# IEEEAdapter_v2.net
KiCad netlist of a schematic drawn in EAGLE
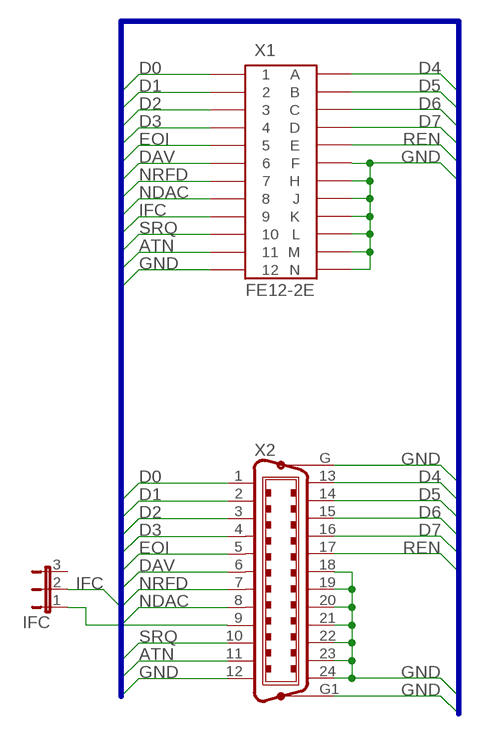
[diagram p0: schematic, sheet 1]

(export (version "E")
  (design (tool "Eeschema 10.0.6"))
  (components
    (comp (ref "IFC")
      (value "JP2E")
      (footprint "eagle-import:JP2")
      (libsource (lib "eagle-import") (part "JP2E"))
    )
    (comp (ref "X1")
      (value "FE12-2E")
      (footprint "eagle-import:FE12-2_SHORT")
      (libsource (lib "eagle-import") (part "FE12-2E"))
    )
    (comp (ref "X2")
      (value "C24HP")
      (footprint "eagle-import:24HP")
      (libsource (lib "eagle-import") (part "C24HP"))
    )
  )
  (nets
    (net (code "1") (name "/ATN") (class "Default")
      (node (ref "X1") (pin "11") (pinfunction "11_11") (pintype "passive"))
      (node (ref "X2") (pin "11") (pinfunction "11_11") (pintype "passive"))
    )
    (net (code "2") (name "/D0") (class "Default")
      (node (ref "X1") (pin "1") (pinfunction "1_1") (pintype "passive"))
      (node (ref "X2") (pin "1") (pinfunction "1_1") (pintype "passive"))
    )
    (net (code "3") (name "/D1") (class "Default")
      (node (ref "X1") (pin "2") (pinfunction "2_2") (pintype "passive"))
      (node (ref "X2") (pin "2") (pinfunction "2_2") (pintype "passive"))
    )
    (net (code "4") (name "/D2") (class "Default")
      (node (ref "X1") (pin "3") (pinfunction "3_3") (pintype "passive"))
      (node (ref "X2") (pin "3") (pinfunction "3_3") (pintype "passive"))
    )
    (net (code "5") (name "/D3") (class "Default")
      (node (ref "X1") (pin "4") (pinfunction "4_4") (pintype "passive"))
      (node (ref "X2") (pin "4") (pinfunction "4_4") (pintype "passive"))
    )
    (net (code "6") (name "/D4") (class "Default")
      (node (ref "X1") (pin "A") (pinfunction "A_A") (pintype "passive"))
      (node (ref "X2") (pin "13") (pinfunction "13_13") (pintype "passive"))
    )
    (net (code "7") (name "/D5") (class "Default")
      (node (ref "X1") (pin "B") (pinfunction "B_B") (pintype "passive"))
      (node (ref "X2") (pin "14") (pinfunction "14_14") (pintype "passive"))
    )
    (net (code "8") (name "/D6") (class "Default")
      (node (ref "X1") (pin "C") (pinfunction "C_C") (pintype "passive"))
      (node (ref "X2") (pin "15") (pinfunction "15_15") (pintype "passive"))
    )
    (net (code "9") (name "/D7") (class "Default")
      (node (ref "X1") (pin "D") (pinfunction "D_D") (pintype "passive"))
      (node (ref "X2") (pin "16") (pinfunction "16_16") (pintype "passive"))
    )
    (net (code "10") (name "/DAV") (class "Default")
      (node (ref "X1") (pin "6") (pinfunction "6_6") (pintype "passive"))
      (node (ref "X2") (pin "6") (pinfunction "6_6") (pintype "passive"))
    )
    (net (code "11") (name "/EOI") (class "Default")
      (node (ref "X1") (pin "5") (pinfunction "5_5") (pintype "passive"))
      (node (ref "X2") (pin "5") (pinfunction "5_5") (pintype "passive"))
    )
    (net (code "12") (name "/GND") (class "Default")
      (node (ref "X1") (pin "12") (pinfunction "12_12") (pintype "passive"))
      (node (ref "X1") (pin "F") (pinfunction "F_F") (pintype "passive"))
      (node (ref "X1") (pin "H") (pinfunction "H_H") (pintype "passive"))
      (node (ref "X1") (pin "J") (pinfunction "J_J") (pintype "passive"))
      (node (ref "X1") (pin "K") (pinfunction "K_K") (pintype "passive"))
      (node (ref "X1") (pin "L") (pinfunction "L_L") (pintype "passive"))
      (node (ref "X1") (pin "M") (pinfunction "M_M") (pintype "passive"))
      (node (ref "X1") (pin "N") (pinfunction "N_N") (pintype "passive"))
      (node (ref "X2") (pin "12") (pinfunction "12_12") (pintype "passive"))
      (node (ref "X2") (pin "18") (pinfunction "18_18") (pintype "passive"))
      (node (ref "X2") (pin "19") (pinfunction "19_19") (pintype "passive"))
      (node (ref "X2") (pin "20") (pinfunction "20_20") (pintype "passive"))
      (node (ref "X2") (pin "21") (pinfunction "21_21") (pintype "passive"))
      (node (ref "X2") (pin "22") (pinfunction "22_22") (pintype "passive"))
      (node (ref "X2") (pin "23") (pinfunction "23_23") (pintype "passive"))
      (node (ref "X2") (pin "24") (pinfunction "24_24") (pintype "passive"))
      (node (ref "X2") (pin "G") (pinfunction "G_G") (pintype "passive"))
      (node (ref "X2") (pin "G1") (pinfunction "G1_G1") (pintype "passive"))
    )
    (net (code "13") (name "/IFC") (class "Default")
      (node (ref "IFC") (pin "2") (pinfunction "2_2") (pintype "passive"))
      (node (ref "X1") (pin "9") (pinfunction "9_9") (pintype "passive"))
    )
    (net (code "14") (name "/NDAC") (class "Default")
      (node (ref "X1") (pin "8") (pinfunction "8_8") (pintype "passive"))
      (node (ref "X2") (pin "8") (pinfunction "8_8") (pintype "passive"))
    )
    (net (code "15") (name "/NRFD") (class "Default")
      (node (ref "X1") (pin "7") (pinfunction "7_7") (pintype "passive"))
      (node (ref "X2") (pin "7") (pinfunction "7_7") (pintype "passive"))
    )
    (net (code "16") (name "/REN") (class "Default")
      (node (ref "X1") (pin "E") (pinfunction "E_E") (pintype "passive"))
      (node (ref "X2") (pin "17") (pinfunction "17_17") (pintype "passive"))
    )
    (net (code "17") (name "/SRQ") (class "Default")
      (node (ref "X1") (pin "10") (pinfunction "10_10") (pintype "passive"))
      (node (ref "X2") (pin "10") (pinfunction "10_10") (pintype "passive"))
    )
    (net (code "18") (name "Net-(IFC-Pad1)") (class "Default")
      (node (ref "IFC") (pin "1") (pinfunction "1_1") (pintype "passive"))
      (node (ref "X2") (pin "9") (pinfunction "9_9") (pintype "passive"))
    )
    (net (code "19") (name "unconnected-(IFC-Pad3)") (class "Default")
      (node (ref "IFC") (pin "3") (pinfunction "3_3") (pintype "passive"))
    )
  )
)
